# IotaWatt.net
KiCad netlist of a schematic drawn in EAGLE
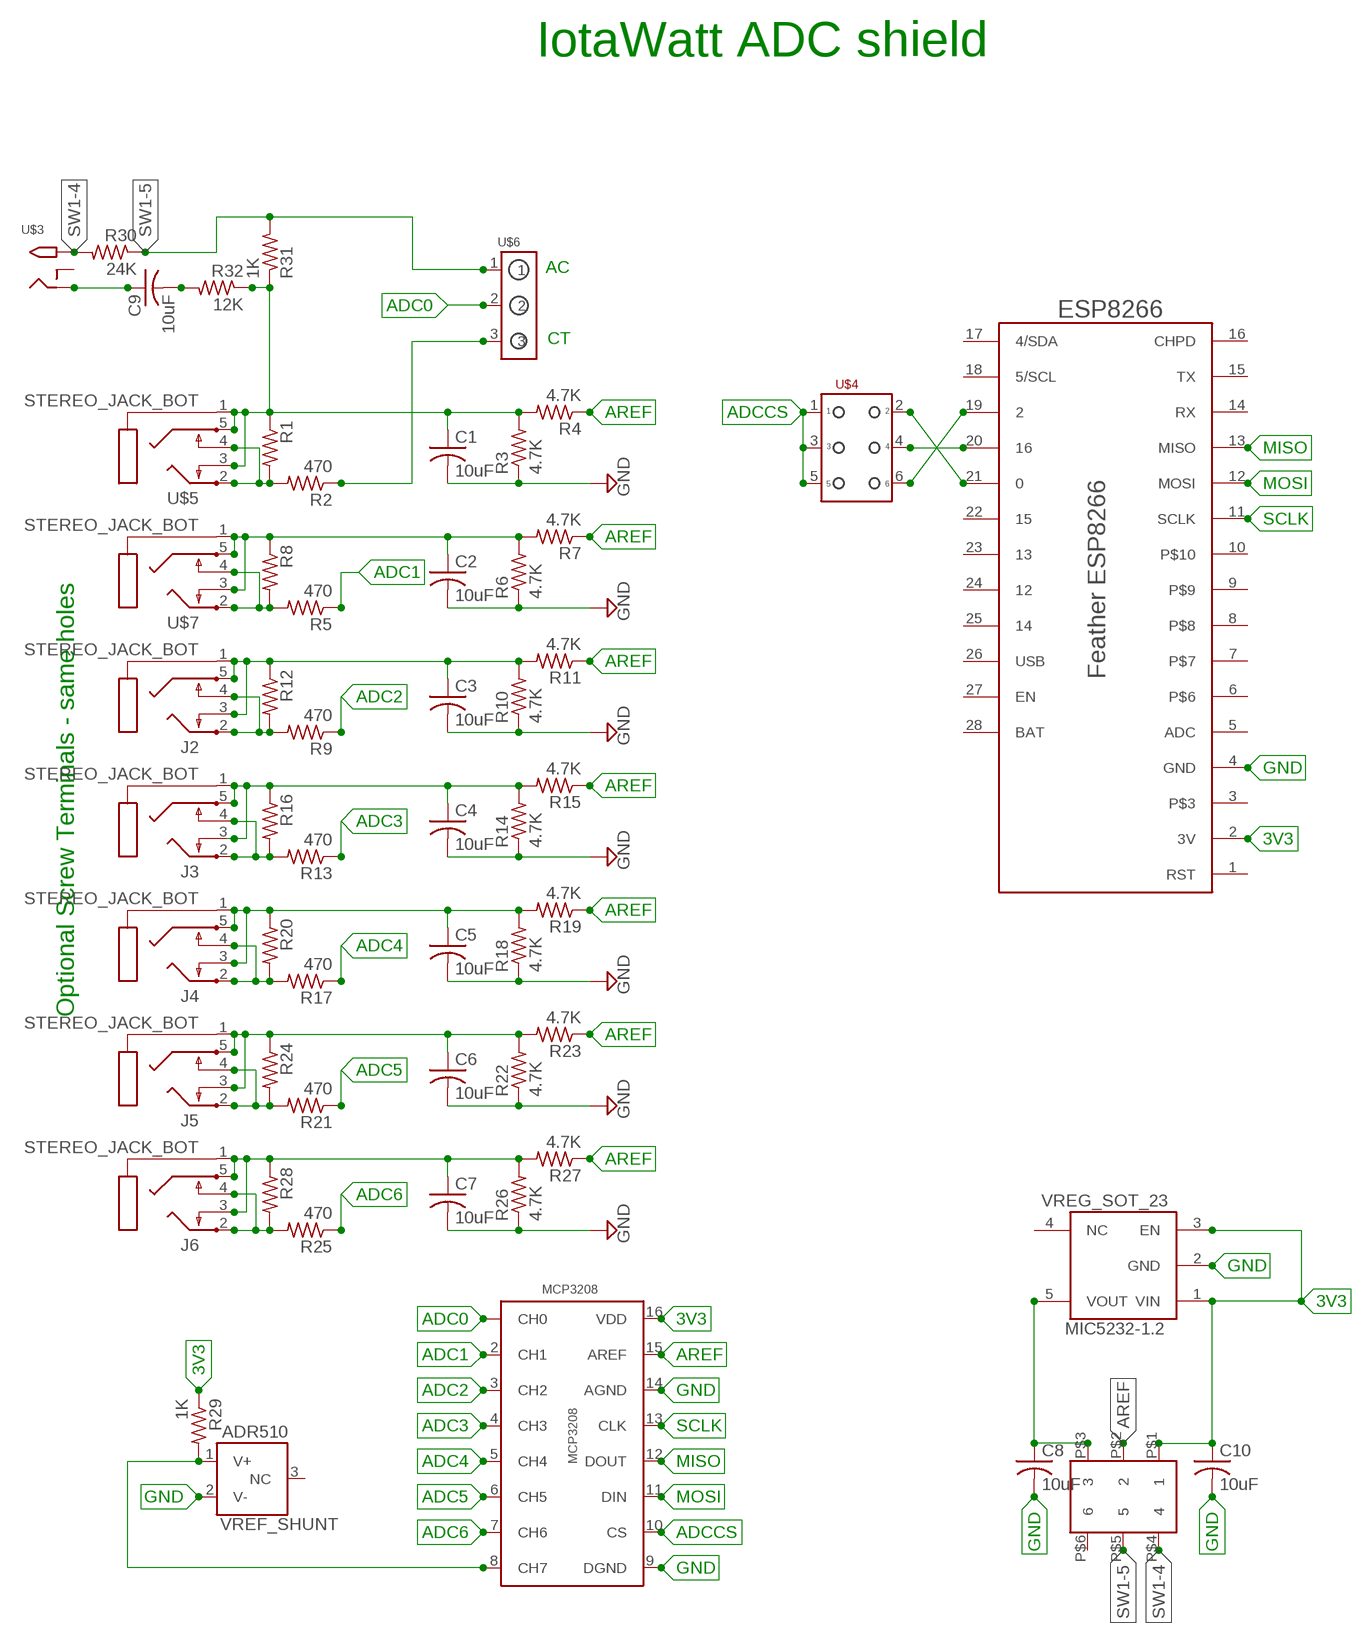
[diagram p0: schematic, sheet 1]

(export (version "E")
  (design (tool "Eeschema 10.0.6"))
  (components
    (comp (ref "ADR510")
      (value "VREF_SHUNT")
      (footprint "eagle-import:SOT23_3")
      (libsource (lib "eagle-import") (part "VREF_SHUNT"))
    )
    (comp (ref "C1")
      (value "10uF")
      (footprint "eagle-import:C0805")
      (libsource (lib "eagle-import") (part "C-USC0805"))
    )
    (comp (ref "C2")
      (value "10uF")
      (footprint "eagle-import:C0805")
      (libsource (lib "eagle-import") (part "C-USC0805"))
    )
    (comp (ref "C3")
      (value "10uF")
      (footprint "eagle-import:C0805")
      (libsource (lib "eagle-import") (part "C-USC0805"))
    )
    (comp (ref "C4")
      (value "10uF")
      (footprint "eagle-import:C0805")
      (libsource (lib "eagle-import") (part "C-USC0805"))
    )
    (comp (ref "C5")
      (value "10uF")
      (footprint "eagle-import:C0805")
      (libsource (lib "eagle-import") (part "C-USC0805"))
    )
    (comp (ref "C6")
      (value "10uF")
      (footprint "eagle-import:C0805")
      (libsource (lib "eagle-import") (part "C-USC0805"))
    )
    (comp (ref "C7")
      (value "10uF")
      (footprint "eagle-import:C0805")
      (libsource (lib "eagle-import") (part "C-USC0805"))
    )
    (comp (ref "C8")
      (value "10uF")
      (footprint "eagle-import:C0805")
      (libsource (lib "eagle-import") (part "C-USC0805"))
    )
    (comp (ref "C9")
      (value "10uF")
      (footprint "eagle-import:C0805")
      (libsource (lib "eagle-import") (part "C-USC0805"))
    )
    (comp (ref "C10")
      (value "10uF")
      (footprint "eagle-import:C0805")
      (libsource (lib "eagle-import") (part "C-USC0805"))
    )
    (comp (ref "J2")
      (value "STEREO_JACK_BOT")
      (footprint "eagle-import:STX3100")
      (libsource (lib "eagle-import") (part "STEREO_JACK_BOT"))
    )
    (comp (ref "J3")
      (value "STEREO_JACK_BOT")
      (footprint "eagle-import:STX3100")
      (libsource (lib "eagle-import") (part "STEREO_JACK_BOT"))
    )
    (comp (ref "J4")
      (value "STEREO_JACK_BOT")
      (footprint "eagle-import:STX3100")
      (libsource (lib "eagle-import") (part "STEREO_JACK_BOT"))
    )
    (comp (ref "J5")
      (value "STEREO_JACK_BOT")
      (footprint "eagle-import:STX3100")
      (libsource (lib "eagle-import") (part "STEREO_JACK_BOT"))
    )
    (comp (ref "J6")
      (value "STEREO_JACK_BOT")
      (footprint "eagle-import:STX3100")
      (libsource (lib "eagle-import") (part "STEREO_JACK_BOT"))
    )
    (comp (ref "MCP3208")
      (value "MCP3208")
      (footprint "eagle-import:SOIC_16")
      (libsource (lib "eagle-import") (part "MCP3208"))
    )
    (comp (ref "MIC5232-1.2")
      (value "VREG_SOT_23")
      (footprint "eagle-import:SOT23_5")
      (libsource (lib "eagle-import") (part "VREG_SOT_23"))
    )
    (comp (ref "R1")
      (value "R-US_FLIPFLOP7")
      (footprint "eagle-import:0805-THM-7")
      (libsource (lib "eagle-import") (part "R-US_FLIPFLOP7"))
    )
    (comp (ref "R2")
      (value "470")
      (footprint "eagle-import:R0805")
      (libsource (lib "eagle-import") (part "R-US_R0805"))
    )
    (comp (ref "R3")
      (value "4.7K")
      (footprint "eagle-import:R0805")
      (libsource (lib "eagle-import") (part "R-US_R0805"))
    )
    (comp (ref "R4")
      (value "4.7K")
      (footprint "eagle-import:R0805")
      (libsource (lib "eagle-import") (part "R-US_R0805"))
    )
    (comp (ref "R5")
      (value "470")
      (footprint "eagle-import:R0805")
      (libsource (lib "eagle-import") (part "R-US_R0805"))
    )
    (comp (ref "R6")
      (value "4.7K")
      (footprint "eagle-import:R0805")
      (libsource (lib "eagle-import") (part "R-US_R0805"))
    )
    (comp (ref "R7")
      (value "4.7K")
      (footprint "eagle-import:R0805")
      (libsource (lib "eagle-import") (part "R-US_R0805"))
    )
    (comp (ref "R8")
      (value "R-US_FLIPFLOP7")
      (footprint "eagle-import:0805-THM-7")
      (libsource (lib "eagle-import") (part "R-US_FLIPFLOP7"))
    )
    (comp (ref "R9")
      (value "470")
      (footprint "eagle-import:R0805")
      (libsource (lib "eagle-import") (part "R-US_R0805"))
    )
    (comp (ref "R10")
      (value "4.7K")
      (footprint "eagle-import:R0805")
      (libsource (lib "eagle-import") (part "R-US_R0805"))
    )
    (comp (ref "R11")
      (value "4.7K")
      (footprint "eagle-import:R0805")
      (libsource (lib "eagle-import") (part "R-US_R0805"))
    )
    (comp (ref "R12")
      (value "R-US_FLIPFLOP7")
      (footprint "eagle-import:0805-THM-7")
      (libsource (lib "eagle-import") (part "R-US_FLIPFLOP7"))
    )
    (comp (ref "R13")
      (value "470")
      (footprint "eagle-import:R0805")
      (libsource (lib "eagle-import") (part "R-US_R0805"))
    )
    (comp (ref "R14")
      (value "4.7K")
      (footprint "eagle-import:R0805")
      (libsource (lib "eagle-import") (part "R-US_R0805"))
    )
    (comp (ref "R15")
      (value "4.7K")
      (footprint "eagle-import:R0805")
      (libsource (lib "eagle-import") (part "R-US_R0805"))
    )
    (comp (ref "R16")
      (value "R-US_FLIPFLOP7")
      (footprint "eagle-import:0805-THM-7")
      (libsource (lib "eagle-import") (part "R-US_FLIPFLOP7"))
    )
    (comp (ref "R17")
      (value "470")
      (footprint "eagle-import:R0805")
      (libsource (lib "eagle-import") (part "R-US_R0805"))
    )
    (comp (ref "R18")
      (value "4.7K")
      (footprint "eagle-import:R0805")
      (libsource (lib "eagle-import") (part "R-US_R0805"))
    )
    (comp (ref "R19")
      (value "4.7K")
      (footprint "eagle-import:R0805")
      (libsource (lib "eagle-import") (part "R-US_R0805"))
    )
    (comp (ref "R20")
      (value "R-US_FLIPFLOP7")
      (footprint "eagle-import:0805-THM-7")
      (libsource (lib "eagle-import") (part "R-US_FLIPFLOP7"))
    )
    (comp (ref "R21")
      (value "470")
      (footprint "eagle-import:R0805")
      (libsource (lib "eagle-import") (part "R-US_R0805"))
    )
    (comp (ref "R22")
      (value "4.7K")
      (footprint "eagle-import:R0805")
      (libsource (lib "eagle-import") (part "R-US_R0805"))
    )
    (comp (ref "R23")
      (value "4.7K")
      (footprint "eagle-import:R0805")
      (libsource (lib "eagle-import") (part "R-US_R0805"))
    )
    (comp (ref "R24")
      (value "R-US_FLIPFLOP7")
      (footprint "eagle-import:0805-THM-7")
      (libsource (lib "eagle-import") (part "R-US_FLIPFLOP7"))
    )
    (comp (ref "R25")
      (value "470")
      (footprint "eagle-import:R0805")
      (libsource (lib "eagle-import") (part "R-US_R0805"))
    )
    (comp (ref "R26")
      (value "4.7K")
      (footprint "eagle-import:R0805")
      (libsource (lib "eagle-import") (part "R-US_R0805"))
    )
    (comp (ref "R27")
      (value "4.7K")
      (footprint "eagle-import:R0805")
      (libsource (lib "eagle-import") (part "R-US_R0805"))
    )
    (comp (ref "R28")
      (value "R-US_FLIPFLOP7")
      (footprint "eagle-import:0805-THM-7")
      (libsource (lib "eagle-import") (part "R-US_FLIPFLOP7"))
    )
    (comp (ref "R29")
      (value "1K")
      (footprint "eagle-import:R0805")
      (libsource (lib "eagle-import") (part "R-US_R0805"))
    )
    (comp (ref "R30")
      (value "24K")
      (footprint "eagle-import:R0805")
      (libsource (lib "eagle-import") (part "R-US_R0805"))
    )
    (comp (ref "R31")
      (value "1K")
      (footprint "eagle-import:R0805")
      (libsource (lib "eagle-import") (part "R-US_R0805"))
    )
    (comp (ref "R32")
      (value "12K")
      (footprint "eagle-import:R0805")
      (libsource (lib "eagle-import") (part "R-US_R0805"))
    )
    (comp (ref "U$1")
      (value "ESP8266FEATHER")
      (footprint "eagle-import:FEATHERWING")
      (libsource (lib "eagle-import") (part "ESP8266FEATHER"))
    )
    (comp (ref "U$3")
      (value "2.1MMJACKBOTTHM")
      (footprint "eagle-import:PJ-102A-BOT")
      (libsource (lib "eagle-import") (part "2.1MMJACKBOTTHM"))
    )
    (comp (ref "U$4")
      (value "HEADER_2X3")
      (footprint "eagle-import:HEADER_2X3")
      (libsource (lib "eagle-import") (part "HEADER_2X3"))
    )
    (comp (ref "U$5")
      (value "STEREO_JACK_BOT")
      (footprint "eagle-import:STX3100")
      (libsource (lib "eagle-import") (part "STEREO_JACK_BOT"))
    )
    (comp (ref "U$6")
      (value "HEADER_1X3")
      (footprint "eagle-import:HEADER_1X3")
      (libsource (lib "eagle-import") (part "HEADER_1X3"))
    )
    (comp (ref "U$7")
      (value "STEREO_JACK_BOT")
      (footprint "eagle-import:STX3100")
      (libsource (lib "eagle-import") (part "STEREO_JACK_BOT"))
    )
    (comp (ref "U$8")
      (value "DPDT_SMT_SW")
      (footprint "eagle-import:JS202011SCQN")
      (libsource (lib "eagle-import") (part "DPDT_SMT_SW"))
    )
  )
  (nets
    (net (code "1") (name "3V3") (class "Default")
      (node (ref "C10") (pin "1") (pinfunction "1_1") (pintype "passive"))
      (node (ref "MCP3208") (pin "16") (pinfunction "VDD_16") (pintype "bidirectional"))
      (node (ref "MIC5232-1.2") (pin "1") (pinfunction "VIN_1") (pintype "bidirectional"))
      (node (ref "MIC5232-1.2") (pin "3") (pinfunction "EN_3") (pintype "bidirectional"))
      (node (ref "R29") (pin "1") (pinfunction "1_1") (pintype "passive"))
      (node (ref "U$1") (pin "2") (pinfunction "3V_2") (pintype "bidirectional"))
      (node (ref "U$8") (pin "P$1") (pinfunction "1_P$1") (pintype "bidirectional"))
    )
    (net (code "2") (name "ADC0") (class "Default")
      (node (ref "MCP3208") (pin "1") (pinfunction "CH0_1") (pintype "input"))
      (node (ref "U$6") (pin "2") (pinfunction "2_2") (pintype "bidirectional"))
    )
    (net (code "3") (name "ADC1") (class "Default")
      (node (ref "MCP3208") (pin "2") (pinfunction "CH1_2") (pintype "input"))
      (node (ref "R5") (pin "1") (pinfunction "1_1") (pintype "passive"))
    )
    (net (code "4") (name "ADC2") (class "Default")
      (node (ref "MCP3208") (pin "3") (pinfunction "CH2_3") (pintype "input"))
      (node (ref "R9") (pin "1") (pinfunction "1_1") (pintype "passive"))
    )
    (net (code "5") (name "ADC3") (class "Default")
      (node (ref "MCP3208") (pin "4") (pinfunction "CH3_4") (pintype "input"))
      (node (ref "R13") (pin "1") (pinfunction "1_1") (pintype "passive"))
    )
    (net (code "6") (name "ADC4") (class "Default")
      (node (ref "MCP3208") (pin "5") (pinfunction "CH4_5") (pintype "bidirectional"))
      (node (ref "R17") (pin "1") (pinfunction "1_1") (pintype "passive"))
    )
    (net (code "7") (name "ADC5") (class "Default")
      (node (ref "MCP3208") (pin "6") (pinfunction "CH5_6") (pintype "bidirectional"))
      (node (ref "R21") (pin "1") (pinfunction "1_1") (pintype "passive"))
    )
    (net (code "8") (name "ADC6") (class "Default")
      (node (ref "MCP3208") (pin "7") (pinfunction "CH6_7") (pintype "input"))
      (node (ref "R25") (pin "1") (pinfunction "1_1") (pintype "passive"))
    )
    (net (code "9") (name "ADCCS") (class "Default")
      (node (ref "MCP3208") (pin "10") (pinfunction "CS_10") (pintype "input"))
      (node (ref "U$4") (pin "1") (pinfunction "P$1_1") (pintype "bidirectional"))
      (node (ref "U$4") (pin "3") (pinfunction "P$3_3") (pintype "bidirectional"))
      (node (ref "U$4") (pin "5") (pinfunction "P$5_5") (pintype "bidirectional"))
    )
    (net (code "10") (name "AREF") (class "Default")
      (node (ref "MCP3208") (pin "15") (pinfunction "AREF_15") (pintype "input"))
      (node (ref "R11") (pin "1") (pinfunction "1_1") (pintype "passive"))
      (node (ref "R15") (pin "1") (pinfunction "1_1") (pintype "passive"))
      (node (ref "R19") (pin "1") (pinfunction "1_1") (pintype "passive"))
      (node (ref "R23") (pin "1") (pinfunction "1_1") (pintype "passive"))
      (node (ref "R27") (pin "1") (pinfunction "1_1") (pintype "passive"))
      (node (ref "R4") (pin "1") (pinfunction "1_1") (pintype "passive"))
      (node (ref "R7") (pin "1") (pinfunction "1_1") (pintype "passive"))
      (node (ref "U$8") (pin "P$2") (pinfunction "2_P$2") (pintype "bidirectional"))
    )
    (net (code "11") (name "GND") (class "Default")
      (node (ref "ADR510") (pin "2") (pinfunction "V-_2") (pintype "bidirectional"))
      (node (ref "C1") (pin "2") (pinfunction "2_2") (pintype "passive"))
      (node (ref "C10") (pin "2") (pinfunction "2_2") (pintype "passive"))
      (node (ref "C2") (pin "2") (pinfunction "2_2") (pintype "passive"))
      (node (ref "C3") (pin "2") (pinfunction "2_2") (pintype "passive"))
      (node (ref "C4") (pin "2") (pinfunction "2_2") (pintype "passive"))
      (node (ref "C5") (pin "2") (pinfunction "2_2") (pintype "passive"))
      (node (ref "C6") (pin "2") (pinfunction "2_2") (pintype "passive"))
      (node (ref "C7") (pin "2") (pinfunction "2_2") (pintype "passive"))
      (node (ref "C8") (pin "2") (pinfunction "2_2") (pintype "passive"))
      (node (ref "MCP3208") (pin "14") (pinfunction "AGND_14") (pintype "input"))
      (node (ref "MCP3208") (pin "9") (pinfunction "DGND_9") (pintype "bidirectional"))
      (node (ref "MIC5232-1.2") (pin "2") (pinfunction "GND_2") (pintype "bidirectional"))
      (node (ref "R10") (pin "1") (pinfunction "1_1") (pintype "passive"))
      (node (ref "R14") (pin "1") (pinfunction "1_1") (pintype "passive"))
      (node (ref "R18") (pin "1") (pinfunction "1_1") (pintype "passive"))
      (node (ref "R22") (pin "1") (pinfunction "1_1") (pintype "passive"))
      (node (ref "R26") (pin "1") (pinfunction "1_1") (pintype "passive"))
      (node (ref "R3") (pin "1") (pinfunction "1_1") (pintype "passive"))
      (node (ref "R6") (pin "1") (pinfunction "1_1") (pintype "passive"))
      (node (ref "U$1") (pin "4") (pinfunction "GND_4") (pintype "bidirectional"))
    )
    (net (code "12") (name "MISO") (class "Default")
      (node (ref "MCP3208") (pin "12") (pinfunction "DOUT_12") (pintype "bidirectional"))
      (node (ref "U$1") (pin "13") (pinfunction "MISO_13") (pintype "bidirectional"))
    )
    (net (code "13") (name "MOSI") (class "Default")
      (node (ref "MCP3208") (pin "11") (pinfunction "DIN_11") (pintype "input"))
      (node (ref "U$1") (pin "12") (pinfunction "MOSI_12") (pintype "bidirectional"))
    )
    (net (code "14") (name "Net-(ADR510-V+)") (class "Default")
      (node (ref "ADR510") (pin "1") (pinfunction "V+_1") (pintype "bidirectional"))
      (node (ref "MCP3208") (pin "8") (pinfunction "CH7_8") (pintype "bidirectional"))
      (node (ref "R29") (pin "2") (pinfunction "2_2") (pintype "passive"))
    )
    (net (code "15") (name "Net-(C9-Pad1)") (class "Default")
      (node (ref "C9") (pin "1") (pinfunction "1_1") (pintype "passive"))
      (node (ref "U$3") (pin "RING") (pinfunction "RING_RING") (pintype "bidirectional"))
    )
    (net (code "16") (name "Net-(C9-Pad2)") (class "Default")
      (node (ref "C9") (pin "2") (pinfunction "2_2") (pintype "passive"))
      (node (ref "R32") (pin "2") (pinfunction "2_2") (pintype "passive"))
    )
    (net (code "17") (name "Net-(J2-2)") (class "Default")
      (node (ref "C3") (pin "1") (pinfunction "1_1") (pintype "passive"))
      (node (ref "J2") (pin "1") (pinfunction "1_1") (pintype "passive"))
      (node (ref "J2") (pin "3") (pinfunction "4_3") (pintype "passive"))
      (node (ref "J2") (pin "5") (pinfunction "2_5") (pintype "passive"))
      (node (ref "R10") (pin "2") (pinfunction "2_2") (pintype "passive"))
      (node (ref "R11") (pin "2") (pinfunction "2_2") (pintype "passive"))
      (node (ref "R12") (pin "1") (pinfunction "1_1") (pintype "passive"))
    )
    (net (code "18") (name "Net-(J2-3)") (class "Default")
      (node (ref "J2") (pin "2") (pinfunction "5_2") (pintype "passive"))
      (node (ref "J2") (pin "4") (pinfunction "3_4") (pintype "passive"))
      (node (ref "R12") (pin "2") (pinfunction "2_2") (pintype "passive"))
      (node (ref "R9") (pin "2") (pinfunction "2_2") (pintype "passive"))
    )
    (net (code "19") (name "Net-(J3-2)") (class "Default")
      (node (ref "C4") (pin "1") (pinfunction "1_1") (pintype "passive"))
      (node (ref "J3") (pin "1") (pinfunction "1_1") (pintype "passive"))
      (node (ref "J3") (pin "3") (pinfunction "4_3") (pintype "passive"))
      (node (ref "J3") (pin "5") (pinfunction "2_5") (pintype "passive"))
      (node (ref "R14") (pin "2") (pinfunction "2_2") (pintype "passive"))
      (node (ref "R15") (pin "2") (pinfunction "2_2") (pintype "passive"))
      (node (ref "R16") (pin "1") (pinfunction "1_1") (pintype "passive"))
    )
    (net (code "20") (name "Net-(J3-3)") (class "Default")
      (node (ref "J3") (pin "2") (pinfunction "5_2") (pintype "passive"))
      (node (ref "J3") (pin "4") (pinfunction "3_4") (pintype "passive"))
      (node (ref "R13") (pin "2") (pinfunction "2_2") (pintype "passive"))
      (node (ref "R16") (pin "2") (pinfunction "2_2") (pintype "passive"))
    )
    (net (code "21") (name "Net-(J4-2)") (class "Default")
      (node (ref "C5") (pin "1") (pinfunction "1_1") (pintype "passive"))
      (node (ref "J4") (pin "1") (pinfunction "1_1") (pintype "passive"))
      (node (ref "J4") (pin "3") (pinfunction "4_3") (pintype "passive"))
      (node (ref "J4") (pin "5") (pinfunction "2_5") (pintype "passive"))
      (node (ref "R18") (pin "2") (pinfunction "2_2") (pintype "passive"))
      (node (ref "R19") (pin "2") (pinfunction "2_2") (pintype "passive"))
      (node (ref "R20") (pin "1") (pinfunction "1_1") (pintype "passive"))
    )
    (net (code "22") (name "Net-(J4-3)") (class "Default")
      (node (ref "J4") (pin "2") (pinfunction "5_2") (pintype "passive"))
      (node (ref "J4") (pin "4") (pinfunction "3_4") (pintype "passive"))
      (node (ref "R17") (pin "2") (pinfunction "2_2") (pintype "passive"))
      (node (ref "R20") (pin "2") (pinfunction "2_2") (pintype "passive"))
    )
    (net (code "23") (name "Net-(J5-2)") (class "Default")
      (node (ref "C6") (pin "1") (pinfunction "1_1") (pintype "passive"))
      (node (ref "J5") (pin "1") (pinfunction "1_1") (pintype "passive"))
      (node (ref "J5") (pin "3") (pinfunction "4_3") (pintype "passive"))
      (node (ref "J5") (pin "5") (pinfunction "2_5") (pintype "passive"))
      (node (ref "R22") (pin "2") (pinfunction "2_2") (pintype "passive"))
      (node (ref "R23") (pin "2") (pinfunction "2_2") (pintype "passive"))
      (node (ref "R24") (pin "1") (pinfunction "1_1") (pintype "passive"))
    )
    (net (code "24") (name "Net-(J5-3)") (class "Default")
      (node (ref "J5") (pin "2") (pinfunction "5_2") (pintype "passive"))
      (node (ref "J5") (pin "4") (pinfunction "3_4") (pintype "passive"))
      (node (ref "R21") (pin "2") (pinfunction "2_2") (pintype "passive"))
      (node (ref "R24") (pin "2") (pinfunction "2_2") (pintype "passive"))
    )
    (net (code "25") (name "Net-(J6-2)") (class "Default")
      (node (ref "C7") (pin "1") (pinfunction "1_1") (pintype "passive"))
      (node (ref "J6") (pin "1") (pinfunction "1_1") (pintype "passive"))
      (node (ref "J6") (pin "3") (pinfunction "4_3") (pintype "passive"))
      (node (ref "J6") (pin "5") (pinfunction "2_5") (pintype "passive"))
      (node (ref "R26") (pin "2") (pinfunction "2_2") (pintype "passive"))
      (node (ref "R27") (pin "2") (pinfunction "2_2") (pintype "passive"))
      (node (ref "R28") (pin "1") (pinfunction "1_1") (pintype "passive"))
    )
    (net (code "26") (name "Net-(J6-3)") (class "Default")
      (node (ref "J6") (pin "2") (pinfunction "5_2") (pintype "passive"))
      (node (ref "J6") (pin "4") (pinfunction "3_4") (pintype "passive"))
      (node (ref "R25") (pin "2") (pinfunction "2_2") (pintype "passive"))
      (node (ref "R28") (pin "2") (pinfunction "2_2") (pintype "passive"))
    )
    (net (code "27") (name "Net-(MIC5232-1.2-VOUT)") (class "Default")
      (node (ref "C8") (pin "1") (pinfunction "1_1") (pintype "passive"))
      (node (ref "MIC5232-1.2") (pin "5") (pinfunction "VOUT_5") (pintype "bidirectional"))
      (node (ref "U$8") (pin "P$3") (pinfunction "3_P$3") (pintype "bidirectional"))
    )
    (net (code "28") (name "Net-(R2-Pad1)") (class "Default")
      (node (ref "R2") (pin "1") (pinfunction "1_1") (pintype "passive"))
      (node (ref "U$6") (pin "3") (pinfunction "3_3") (pintype "bidirectional"))
    )
    (net (code "29") (name "Net-(U$1-0)") (class "Default")
      (node (ref "U$1") (pin "21") (pinfunction "0_21") (pintype "bidirectional"))
      (node (ref "U$4") (pin "2") (pinfunction "P$2_2") (pintype "bidirectional"))
    )
    (net (code "30") (name "Net-(U$1-2)") (class "Default")
      (node (ref "U$1") (pin "19") (pinfunction "2_19") (pintype "bidirectional"))
      (node (ref "U$4") (pin "6") (pinfunction "P$6_6") (pintype "bidirectional"))
    )
    (net (code "31") (name "Net-(U$1-16)") (class "Default")
      (node (ref "U$1") (pin "20") (pinfunction "16_20") (pintype "bidirectional"))
      (node (ref "U$4") (pin "4") (pinfunction "P$4_4") (pintype "bidirectional"))
    )
    (net (code "32") (name "Net-(U$5-2)") (class "Default")
      (node (ref "C1") (pin "1") (pinfunction "1_1") (pintype "passive"))
      (node (ref "R1") (pin "1") (pinfunction "1_1") (pintype "passive"))
      (node (ref "R3") (pin "2") (pinfunction "2_2") (pintype "passive"))
      (node (ref "R31") (pin "1") (pinfunction "1_1") (pintype "passive"))
      (node (ref "R32") (pin "1") (pinfunction "1_1") (pintype "passive"))
      (node (ref "R4") (pin "2") (pinfunction "2_2") (pintype "passive"))
      (node (ref "U$5") (pin "1") (pinfunction "1_1") (pintype "passive"))
      (node (ref "U$5") (pin "3") (pinfunction "4_3") (pintype "passive"))
      (node (ref "U$5") (pin "5") (pinfunction "2_5") (pintype "passive"))
    )
    (net (code "33") (name "Net-(U$5-3)") (class "Default")
      (node (ref "R1") (pin "2") (pinfunction "2_2") (pintype "passive"))
      (node (ref "R2") (pin "2") (pinfunction "2_2") (pintype "passive"))
      (node (ref "U$5") (pin "2") (pinfunction "5_2") (pintype "passive"))
      (node (ref "U$5") (pin "4") (pinfunction "3_4") (pintype "passive"))
    )
    (net (code "34") (name "Net-(U$7-2)") (class "Default")
      (node (ref "C2") (pin "1") (pinfunction "1_1") (pintype "passive"))
      (node (ref "R6") (pin "2") (pinfunction "2_2") (pintype "passive"))
      (node (ref "R7") (pin "2") (pinfunction "2_2") (pintype "passive"))
      (node (ref "R8") (pin "1") (pinfunction "1_1") (pintype "passive"))
      (node (ref "U$7") (pin "1") (pinfunction "1_1") (pintype "passive"))
      (node (ref "U$7") (pin "3") (pinfunction "4_3") (pintype "passive"))
      (node (ref "U$7") (pin "5") (pinfunction "2_5") (pintype "passive"))
    )
    (net (code "35") (name "Net-(U$7-3)") (class "Default")
      (node (ref "R5") (pin "2") (pinfunction "2_2") (pintype "passive"))
      (node (ref "R8") (pin "2") (pinfunction "2_2") (pintype "passive"))
      (node (ref "U$7") (pin "2") (pinfunction "5_2") (pintype "passive"))
      (node (ref "U$7") (pin "4") (pinfunction "3_4") (pintype "passive"))
    )
    (net (code "36") (name "SCLK") (class "Default")
      (node (ref "MCP3208") (pin "13") (pinfunction "CLK_13") (pintype "input"))
      (node (ref "U$1") (pin "11") (pinfunction "SCLK_11") (pintype "bidirectional"))
    )
    (net (code "37") (name "SW1-4") (class "Default")
      (node (ref "R30") (pin "2") (pinfunction "2_2") (pintype "passive"))
      (node (ref "U$3") (pin "TIP") (pinfunction "TIP_TIP") (pintype "bidirectional"))
      (node (ref "U$8") (pin "P$4") (pinfunction "4_P$4") (pintype "bidirectional"))
    )
    (net (code "38") (name "SW1-5") (class "Default")
      (node (ref "R30") (pin "1") (pinfunction "1_1") (pintype "passive"))
      (node (ref "R31") (pin "2") (pinfunction "2_2") (pintype "passive"))
      (node (ref "U$6") (pin "1") (pinfunction "1_1") (pintype "bidirectional"))
      (node (ref "U$8") (pin "P$5") (pinfunction "5_P$5") (pintype "bidirectional"))
    )
    (net (code "39") (name "unconnected-(ADR510-NC-Pad3)") (class "Default")
      (node (ref "ADR510") (pin "3") (pinfunction "NC_3") (pintype "bidirectional"))
    )
    (net (code "40") (name "unconnected-(MIC5232-1.2-NC-Pad4)") (class "Default")
      (node (ref "MIC5232-1.2") (pin "4") (pinfunction "NC_4") (pintype "bidirectional"))
    )
    (net (code "41") (name "unconnected-(U$1-4{slash}SDA-Pad17)") (class "Default")
      (node (ref "U$1") (pin "17") (pinfunction "4/SDA_17") (pintype "bidirectional"))
    )
    (net (code "42") (name "unconnected-(U$1-5{slash}SCL-Pad18)") (class "Default")
      (node (ref "U$1") (pin "18") (pinfunction "5/SCL_18") (pintype "bidirectional"))
    )
    (net (code "43") (name "unconnected-(U$1-12-Pad24)") (class "Default")
      (node (ref "U$1") (pin "24") (pinfunction "12_24") (pintype "bidirectional"))
    )
    (net (code "44") (name "unconnected-(U$1-13-Pad23)") (class "Default")
      (node (ref "U$1") (pin "23") (pinfunction "13_23") (pintype "bidirectional"))
    )
    (net (code "45") (name "unconnected-(U$1-14-Pad25)") (class "Default")
      (node (ref "U$1") (pin "25") (pinfunction "14_25") (pintype "bidirectional"))
    )
    (net (code "46") (name "unconnected-(U$1-15-Pad22)") (class "Default")
      (node (ref "U$1") (pin "22") (pinfunction "15_22") (pintype "bidirectional"))
    )
    (net (code "47") (name "unconnected-(U$1-ADC-Pad5)") (class "Default")
      (node (ref "U$1") (pin "5") (pinfunction "ADC_5") (pintype "bidirectional"))
    )
    (net (code "48") (name "unconnected-(U$1-BAT-Pad28)") (class "Default")
      (node (ref "U$1") (pin "28") (pinfunction "BAT_28") (pintype "bidirectional"))
    )
    (net (code "49") (name "unconnected-(U$1-CHPD-Pad16)") (class "Default")
      (node (ref "U$1") (pin "16") (pinfunction "CHPD_16") (pintype "bidirectional"))
    )
    (net (code "50") (name "unconnected-(U$1-EN-Pad27)") (class "Default")
      (node (ref "U$1") (pin "27") (pinfunction "EN_27") (pintype "bidirectional"))
    )
    (net (code "51") (name "unconnected-(U$1-P$3-Pad3)") (class "Default")
      (node (ref "U$1") (pin "3") (pinfunction "P$3_3") (pintype "bidirectional"))
    )
    (net (code "52") (name "unconnected-(U$1-P$6-Pad6)") (class "Default")
      (node (ref "U$1") (pin "6") (pinfunction "P$6_6") (pintype "bidirectional"))
    )
    (net (code "53") (name "unconnected-(U$1-P$7-Pad7)") (class "Default")
      (node (ref "U$1") (pin "7") (pinfunction "P$7_7") (pintype "bidirectional"))
    )
    (net (code "54") (name "unconnected-(U$1-P$8-Pad8)") (class "Default")
      (node (ref "U$1") (pin "8") (pinfunction "P$8_8") (pintype "bidirectional"))
    )
    (net (code "55") (name "unconnected-(U$1-P$9-Pad9)") (class "Default")
      (node (ref "U$1") (pin "9") (pinfunction "P$9_9") (pintype "bidirectional"))
    )
    (net (code "56") (name "unconnected-(U$1-P$10-Pad10)") (class "Default")
      (node (ref "U$1") (pin "10") (pinfunction "P$10_10") (pintype "bidirectional"))
    )
    (net (code "57") (name "unconnected-(U$1-RST-Pad1)") (class "Default")
      (node (ref "U$1") (pin "1") (pinfunction "RST_1") (pintype "bidirectional"))
    )
    (net (code "58") (name "unconnected-(U$1-RX-Pad14)") (class "Default")
      (node (ref "U$1") (pin "14") (pinfunction "RX_14") (pintype "bidirectional"))
    )
    (net (code "59") (name "unconnected-(U$1-TX-Pad15)") (class "Default")
      (node (ref "U$1") (pin "15") (pinfunction "TX_15") (pintype "bidirectional"))
    )
    (net (code "60") (name "unconnected-(U$1-USB-Pad26)") (class "Default")
      (node (ref "U$1") (pin "26") (pinfunction "USB_26") (pintype "bidirectional"))
    )
    (net (code "61") (name "unconnected-(U$3-PadRING_SW)") (class "Default")
      (node (ref "U$3") (pin "RING_SW") (pinfunction "RING_SW_RING_SW") (pintype "bidirectional"))
    )
    (net (code "62") (name "unconnected-(U$8-6-PadP$6)") (class "Default")
      (node (ref "U$8") (pin "P$6") (pinfunction "6_P$6") (pintype "bidirectional"))
    )
  )
)
